# MicroMultimeter__Sch.net
KiCad netlist of a schematic drawn in Altium Designer
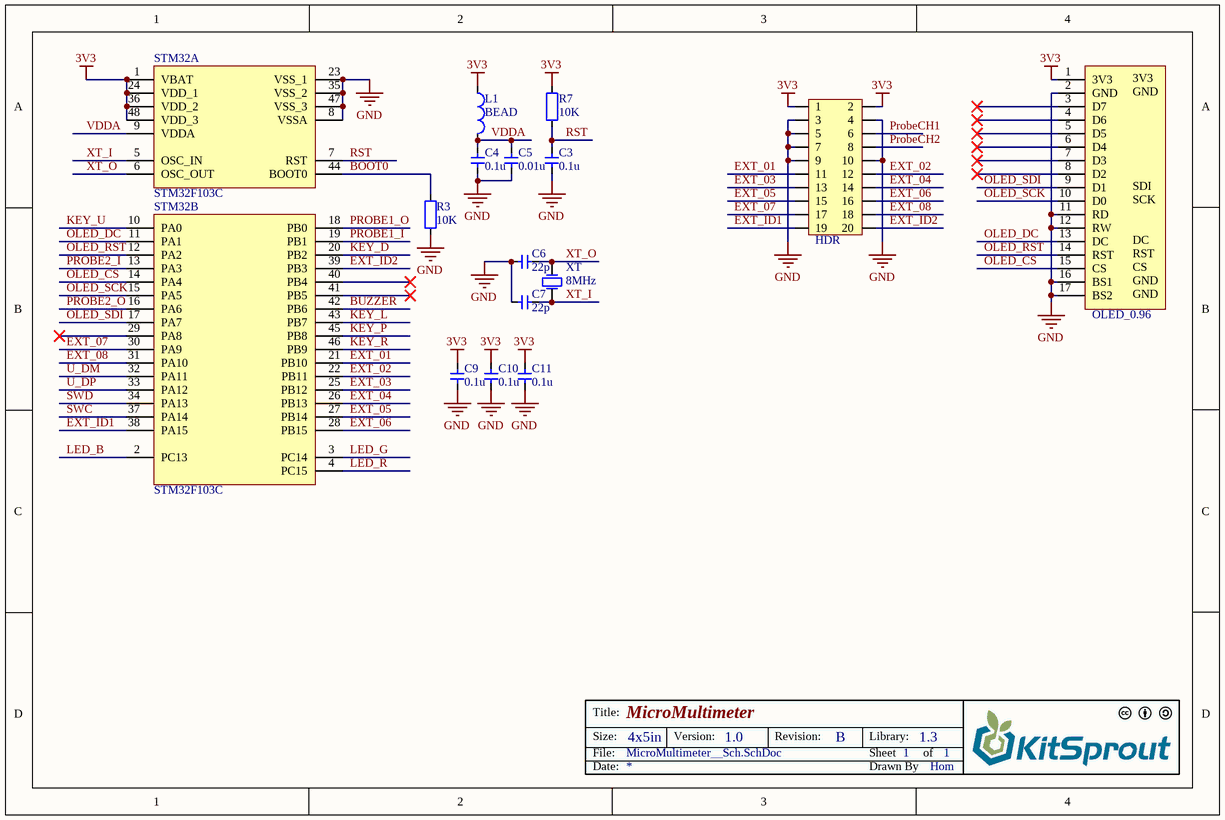
[diagram p0: MicroMultimeter__Sch.SchDoc]

(export (version "E")
  (design (tool "Eeschema 10.0.6"))
  (components
    (comp (ref "C3")
      (value "0.1u")
      (footprint "PCB_PassiveCap:CAP_0603")
      (description "Capacitor")
      (fields (field (name "Comment") "Cap_0603"))
      (libsource (lib "SCH_Passive") (part "Cap_0603"))
    )
    (comp (ref "C4")
      (value "0.1u")
      (footprint "PCB_PassiveCap:CAP_0603")
      (description "Capacitor")
      (fields (field (name "Comment") "Cap_0603"))
      (libsource (lib "SCH_Passive") (part "Cap_0603"))
    )
    (comp (ref "C5")
      (value "0.01u")
      (footprint "PCB_PassiveCap:CAP_0603")
      (description "Capacitor")
      (fields (field (name "Comment") "Cap_0603"))
      (libsource (lib "SCH_Passive") (part "Cap_0603"))
    )
    (comp (ref "C6")
      (value "22p")
      (footprint "PCB_PassiveCap:CAP_0603")
      (description "Capacitor")
      (fields (field (name "Comment") "Cap_0603"))
      (libsource (lib "SCH_Passive") (part "Cap_0603"))
    )
    (comp (ref "C7")
      (value "22p")
      (footprint "PCB_PassiveCap:CAP_0603")
      (description "Capacitor")
      (fields (field (name "Comment") "Cap_0603"))
      (libsource (lib "SCH_Passive") (part "Cap_0603"))
    )
    (comp (ref "C9")
      (value "0.1u")
      (footprint "PCB_PassiveCap:CAP_0603")
      (description "Capacitor")
      (fields (field (name "Comment") "Cap_0603"))
      (libsource (lib "SCH_Passive") (part "Cap_0603"))
    )
    (comp (ref "C10")
      (value "0.1u")
      (footprint "PCB_PassiveCap:CAP_0603")
      (description "Capacitor")
      (fields (field (name "Comment") "Cap_0603"))
      (libsource (lib "SCH_Passive") (part "Cap_0603"))
    )
    (comp (ref "C11")
      (value "0.1u")
      (footprint "PCB_PassiveCap:CAP_0603")
      (description "Capacitor")
      (fields (field (name "Comment") "Cap_0603"))
      (libsource (lib "SCH_Passive") (part "Cap_0603"))
    )
    (comp (ref "HDR")
      (value "HDR2x10_2.54")
      (footprint "PCB_ConnectorHDR:HDR2X10_2.54_180HF")
      (description "Header")
      (libsource (lib "SCH_ConnectorHDR") (part "HDR2x10_2.54"))
    )
    (comp (ref "L1")
      (value "BEAD")
      (footprint "PCB_PassiveInd:IND_0603")
      (description "Inductor")
      (fields (field (name "Comment") "Ind_0603"))
      (libsource (lib "SCH_Passive") (part "Ind_0603"))
    )
    (comp (ref "OLED_0.96")
      (value "OLED_0.96")
      (footprint "PCB_Module:OLED_0.96_96x64")
      (description "Module")
      (libsource (lib "SCH_Module") (part "OLED_0.96_96*64"))
    )
    (comp (ref "R3")
      (value "10K")
      (footprint "PCB_PassiveRes:RES_0603")
      (description "Resistor")
      (fields (field (name "Comment") "Res_0603"))
      (libsource (lib "SCH_Passive") (part "Res_0603"))
    )
    (comp (ref "R7")
      (value "10K")
      (footprint "PCB_PassiveRes:RES_0603")
      (description "Resistor")
      (fields (field (name "Comment") "Res_0603"))
      (libsource (lib "SCH_Passive") (part "Res_0603"))
    )
    (comp (ref "STM32")
      (value "STM32F103C")
      (footprint "PCB_IntegratedCircuit:LQFP_P0.5_48")
      (description "MCU")
      (libsource (lib "SCH_IntegratedCircuit") (part "STM32F103C"))
    )
    (comp (ref "XT")
      (value "8MHz")
      (footprint "PCB_Oscillator:XT_5032_2")
      (description "Crystal Oscillator")
      (fields (field (name "Comment") "XTAL_5032_2P"))
      (libsource (lib "SCH_Oscillator") (part "XTAL_5032_2P"))
    )
  )
  (nets
    (net (code "1") (name "/BOOT0") (class "Default")
      (node (ref "R3") (pin "2") (pinfunction "2_2") (pintype "passive"))
      (node (ref "STM32") (pin "44") (pinfunction "BOOT0_44") (pintype "passive"))
    )
    (net (code "2") (name "/BUZZER") (class "Default")
      (node (ref "STM32") (pin "42") (pinfunction "PB6_42") (pintype "passive"))
    )
    (net (code "3") (name "/EXT_01") (class "Default")
      (node (ref "HDR") (pin "11") (pinfunction "11_11") (pintype "passive"))
      (node (ref "STM32") (pin "21") (pinfunction "PB10_21") (pintype "passive"))
    )
    (net (code "4") (name "/EXT_02") (class "Default")
      (node (ref "HDR") (pin "12") (pinfunction "12_12") (pintype "passive"))
      (node (ref "STM32") (pin "22") (pinfunction "PB11_22") (pintype "passive"))
    )
    (net (code "5") (name "/EXT_03") (class "Default")
      (node (ref "HDR") (pin "13") (pinfunction "13_13") (pintype "passive"))
      (node (ref "STM32") (pin "25") (pinfunction "PB12_25") (pintype "passive"))
    )
    (net (code "6") (name "/EXT_04") (class "Default")
      (node (ref "HDR") (pin "14") (pinfunction "14_14") (pintype "passive"))
      (node (ref "STM32") (pin "26") (pinfunction "PB13_26") (pintype "passive"))
    )
    (net (code "7") (name "/EXT_05") (class "Default")
      (node (ref "HDR") (pin "15") (pinfunction "15_15") (pintype "passive"))
      (node (ref "STM32") (pin "27") (pinfunction "PB14_27") (pintype "passive"))
    )
    (net (code "8") (name "/EXT_06") (class "Default")
      (node (ref "HDR") (pin "16") (pinfunction "16_16") (pintype "passive"))
      (node (ref "STM32") (pin "28") (pinfunction "PB15_28") (pintype "passive"))
    )
    (net (code "9") (name "/EXT_07") (class "Default")
      (node (ref "HDR") (pin "17") (pinfunction "17_17") (pintype "passive"))
      (node (ref "STM32") (pin "30") (pinfunction "PA9_30") (pintype "passive"))
    )
    (net (code "10") (name "/EXT_08") (class "Default")
      (node (ref "HDR") (pin "18") (pinfunction "18_18") (pintype "passive"))
      (node (ref "STM32") (pin "31") (pinfunction "PA10_31") (pintype "passive"))
    )
    (net (code "11") (name "/EXT_ID1") (class "Default")
      (node (ref "HDR") (pin "19") (pinfunction "19_19") (pintype "passive"))
      (node (ref "STM32") (pin "38") (pinfunction "PA15_38") (pintype "passive"))
    )
    (net (code "12") (name "/EXT_ID2") (class "Default")
      (node (ref "HDR") (pin "20") (pinfunction "20_20") (pintype "passive"))
      (node (ref "STM32") (pin "39") (pinfunction "PB3_39") (pintype "passive"))
    )
    (net (code "13") (name "/KEY_D") (class "Default")
      (node (ref "STM32") (pin "20") (pinfunction "PB2_20") (pintype "passive"))
    )
    (net (code "14") (name "/KEY_L") (class "Default")
      (node (ref "STM32") (pin "43") (pinfunction "PB7_43") (pintype "passive"))
    )
    (net (code "15") (name "/KEY_P") (class "Default")
      (node (ref "STM32") (pin "45") (pinfunction "PB8_45") (pintype "passive"))
    )
    (net (code "16") (name "/KEY_R") (class "Default")
      (node (ref "STM32") (pin "46") (pinfunction "PB9_46") (pintype "passive"))
    )
    (net (code "17") (name "/KEY_U") (class "Default")
      (node (ref "STM32") (pin "10") (pinfunction "PA0_10") (pintype "passive"))
    )
    (net (code "18") (name "/LED_B") (class "Default")
      (node (ref "STM32") (pin "2") (pinfunction "PC13_2") (pintype "passive"))
    )
    (net (code "19") (name "/LED_G") (class "Default")
      (node (ref "STM32") (pin "3") (pinfunction "PC14_3") (pintype "passive"))
    )
    (net (code "20") (name "/LED_R") (class "Default")
      (node (ref "STM32") (pin "4") (pinfunction "PC15_4") (pintype "passive"))
    )
    (net (code "21") (name "/OLED_CS") (class "Default")
      (node (ref "OLED_0.96") (pin "15") (pinfunction "CS_15") (pintype "passive"))
      (node (ref "STM32") (pin "14") (pinfunction "PA4_14") (pintype "passive"))
    )
    (net (code "22") (name "/OLED_DC") (class "Default")
      (node (ref "OLED_0.96") (pin "13") (pinfunction "DC_13") (pintype "passive"))
      (node (ref "STM32") (pin "11") (pinfunction "PA1_11") (pintype "passive"))
    )
    (net (code "23") (name "/OLED_RST") (class "Default")
      (node (ref "OLED_0.96") (pin "14") (pinfunction "RST_14") (pintype "passive"))
      (node (ref "STM32") (pin "12") (pinfunction "PA2_12") (pintype "passive"))
    )
    (net (code "24") (name "/OLED_SCK") (class "Default")
      (node (ref "OLED_0.96") (pin "10") (pinfunction "D0_10") (pintype "passive"))
      (node (ref "STM32") (pin "15") (pinfunction "PA5_15") (pintype "passive"))
    )
    (net (code "25") (name "/OLED_SDI") (class "Default")
      (node (ref "OLED_0.96") (pin "9") (pinfunction "D1_9") (pintype "passive"))
      (node (ref "STM32") (pin "17") (pinfunction "PA7_17") (pintype "passive"))
    )
    (net (code "26") (name "/PROBE1_I") (class "Default")
      (node (ref "STM32") (pin "19") (pinfunction "PB1_19") (pintype "passive"))
    )
    (net (code "27") (name "/PROBE1_O") (class "Default")
      (node (ref "STM32") (pin "18") (pinfunction "PB0_18") (pintype "passive"))
    )
    (net (code "28") (name "/PROBE2_I") (class "Default")
      (node (ref "STM32") (pin "13") (pinfunction "PA3_13") (pintype "passive"))
    )
    (net (code "29") (name "/PROBE2_O") (class "Default")
      (node (ref "STM32") (pin "16") (pinfunction "PA6_16") (pintype "passive"))
    )
    (net (code "30") (name "/ProbeCH1") (class "Default")
      (node (ref "HDR") (pin "6") (pinfunction "6_6") (pintype "passive"))
    )
    (net (code "31") (name "/ProbeCH2") (class "Default")
      (node (ref "HDR") (pin "8") (pinfunction "8_8") (pintype "passive"))
    )
    (net (code "32") (name "/RST") (class "Default")
      (node (ref "C3") (pin "2") (pinfunction "2_2") (pintype "passive"))
      (node (ref "R7") (pin "1") (pinfunction "1_1") (pintype "passive"))
      (node (ref "STM32") (pin "7") (pinfunction "RST_7") (pintype "passive"))
    )
    (net (code "33") (name "/SWC") (class "Default")
      (node (ref "STM32") (pin "37") (pinfunction "PA14_37") (pintype "passive"))
    )
    (net (code "34") (name "/SWD") (class "Default")
      (node (ref "STM32") (pin "34") (pinfunction "PA13_34") (pintype "passive"))
    )
    (net (code "35") (name "/U_DM") (class "Default")
      (node (ref "STM32") (pin "32") (pinfunction "PA11_32") (pintype "passive"))
    )
    (net (code "36") (name "/U_DP") (class "Default")
      (node (ref "STM32") (pin "33") (pinfunction "PA12_33") (pintype "passive"))
    )
    (net (code "37") (name "/VDDA") (class "Default")
      (node (ref "C4") (pin "2") (pinfunction "2_2") (pintype "passive"))
      (node (ref "C5") (pin "2") (pinfunction "2_2") (pintype "passive"))
      (node (ref "L1") (pin "2") (pinfunction "2_2") (pintype "passive"))
      (node (ref "STM32") (pin "9") (pinfunction "VDDA_9") (pintype "passive"))
    )
    (net (code "38") (name "/XT_I") (class "Default")
      (node (ref "C7") (pin "1") (pinfunction "1_1") (pintype "passive"))
      (node (ref "STM32") (pin "5") (pinfunction "OSC_IN_5") (pintype "passive"))
      (node (ref "XT") (pin "1") (pinfunction "OSC1_1") (pintype "passive"))
    )
    (net (code "39") (name "/XT_O") (class "Default")
      (node (ref "C6") (pin "1") (pinfunction "1_1") (pintype "passive"))
      (node (ref "STM32") (pin "6") (pinfunction "OSC_OUT_6") (pintype "passive"))
      (node (ref "XT") (pin "2") (pinfunction "OSC2_2") (pintype "passive"))
    )
    (net (code "40") (name "3V3") (class "Default")
      (node (ref "C10") (pin "2") (pinfunction "2_2") (pintype "passive"))
      (node (ref "C11") (pin "2") (pinfunction "2_2") (pintype "passive"))
      (node (ref "C9") (pin "2") (pinfunction "2_2") (pintype "passive"))
      (node (ref "HDR") (pin "1") (pinfunction "1_1") (pintype "passive"))
      (node (ref "HDR") (pin "2") (pinfunction "2_2") (pintype "passive"))
      (node (ref "L1") (pin "1") (pinfunction "1_1") (pintype "passive"))
      (node (ref "OLED_0.96") (pin "1") (pinfunction "3V3_1") (pintype "passive"))
      (node (ref "R7") (pin "2") (pinfunction "2_2") (pintype "passive"))
      (node (ref "STM32") (pin "1") (pinfunction "VBAT_1") (pintype "passive"))
      (node (ref "STM32") (pin "24") (pinfunction "VDD_1_24") (pintype "passive"))
      (node (ref "STM32") (pin "36") (pinfunction "VDD_2_36") (pintype "passive"))
      (node (ref "STM32") (pin "48") (pinfunction "VDD_3_48") (pintype "passive"))
    )
    (net (code "41") (name "GND") (class "Default")
      (node (ref "C10") (pin "1") (pinfunction "1_1") (pintype "passive"))
      (node (ref "C11") (pin "1") (pinfunction "1_1") (pintype "passive"))
      (node (ref "C3") (pin "1") (pinfunction "1_1") (pintype "passive"))
      (node (ref "C4") (pin "1") (pinfunction "1_1") (pintype "passive"))
      (node (ref "C5") (pin "1") (pinfunction "1_1") (pintype "passive"))
      (node (ref "C6") (pin "2") (pinfunction "2_2") (pintype "passive"))
      (node (ref "C7") (pin "2") (pinfunction "2_2") (pintype "passive"))
      (node (ref "C9") (pin "1") (pinfunction "1_1") (pintype "passive"))
      (node (ref "HDR") (pin "10") (pinfunction "10_10") (pintype "passive"))
      (node (ref "HDR") (pin "3") (pinfunction "3_3") (pintype "passive"))
      (node (ref "HDR") (pin "4") (pinfunction "4_4") (pintype "passive"))
      (node (ref "HDR") (pin "5") (pinfunction "5_5") (pintype "passive"))
      (node (ref "HDR") (pin "7") (pinfunction "7_7") (pintype "passive"))
      (node (ref "HDR") (pin "9") (pinfunction "9_9") (pintype "passive"))
      (node (ref "OLED_0.96") (pin "11") (pinfunction "RD_11") (pintype "passive"))
      (node (ref "OLED_0.96") (pin "12") (pinfunction "RW_12") (pintype "passive"))
      (node (ref "OLED_0.96") (pin "16") (pinfunction "BS1_16") (pintype "passive"))
      (node (ref "OLED_0.96") (pin "17") (pinfunction "BS2_17") (pintype "passive"))
      (node (ref "OLED_0.96") (pin "2") (pinfunction "GND_2") (pintype "passive"))
      (node (ref "R3") (pin "1") (pinfunction "1_1") (pintype "passive"))
      (node (ref "STM32") (pin "23") (pinfunction "VSS_1_23") (pintype "passive"))
      (node (ref "STM32") (pin "35") (pinfunction "VSS_2_35") (pintype "passive"))
      (node (ref "STM32") (pin "47") (pinfunction "VSS_3_47") (pintype "passive"))
      (node (ref "STM32") (pin "8") (pinfunction "VSSA_8") (pintype "passive"))
    )
    (net (code "42") (name "unconnected-(OLED_0.96-D2-Pad8)") (class "Default")
      (node (ref "OLED_0.96") (pin "8") (pinfunction "D2_8") (pintype "passive+no_connect"))
    )
    (net (code "43") (name "unconnected-(OLED_0.96-D3-Pad7)") (class "Default")
      (node (ref "OLED_0.96") (pin "7") (pinfunction "D3_7") (pintype "passive+no_connect"))
    )
    (net (code "44") (name "unconnected-(OLED_0.96-D4-Pad6)") (class "Default")
      (node (ref "OLED_0.96") (pin "6") (pinfunction "D4_6") (pintype "passive+no_connect"))
    )
    (net (code "45") (name "unconnected-(OLED_0.96-D5-Pad5)") (class "Default")
      (node (ref "OLED_0.96") (pin "5") (pinfunction "D5_5") (pintype "passive+no_connect"))
    )
    (net (code "46") (name "unconnected-(OLED_0.96-D6-Pad4)") (class "Default")
      (node (ref "OLED_0.96") (pin "4") (pinfunction "D6_4") (pintype "passive+no_connect"))
    )
    (net (code "47") (name "unconnected-(OLED_0.96-D7-Pad3)") (class "Default")
      (node (ref "OLED_0.96") (pin "3") (pinfunction "D7_3") (pintype "passive+no_connect"))
    )
    (net (code "48") (name "unconnected-(STM32B-PA8-Pad29)") (class "Default")
      (node (ref "STM32") (pin "29") (pinfunction "PA8_29") (pintype "passive+no_connect"))
    )
    (net (code "49") (name "unconnected-(STM32B-PB4-Pad40)") (class "Default")
      (node (ref "STM32") (pin "40") (pinfunction "PB4_40") (pintype "passive+no_connect"))
    )
    (net (code "50") (name "unconnected-(STM32B-PB5-Pad41)") (class "Default")
      (node (ref "STM32") (pin "41") (pinfunction "PB5_41") (pintype "passive+no_connect"))
    )
  )
)
